# JETSON_AGX_DP-HDMI-USB-GBE.net
KiCad netlist of a schematic drawn in Altium Designer
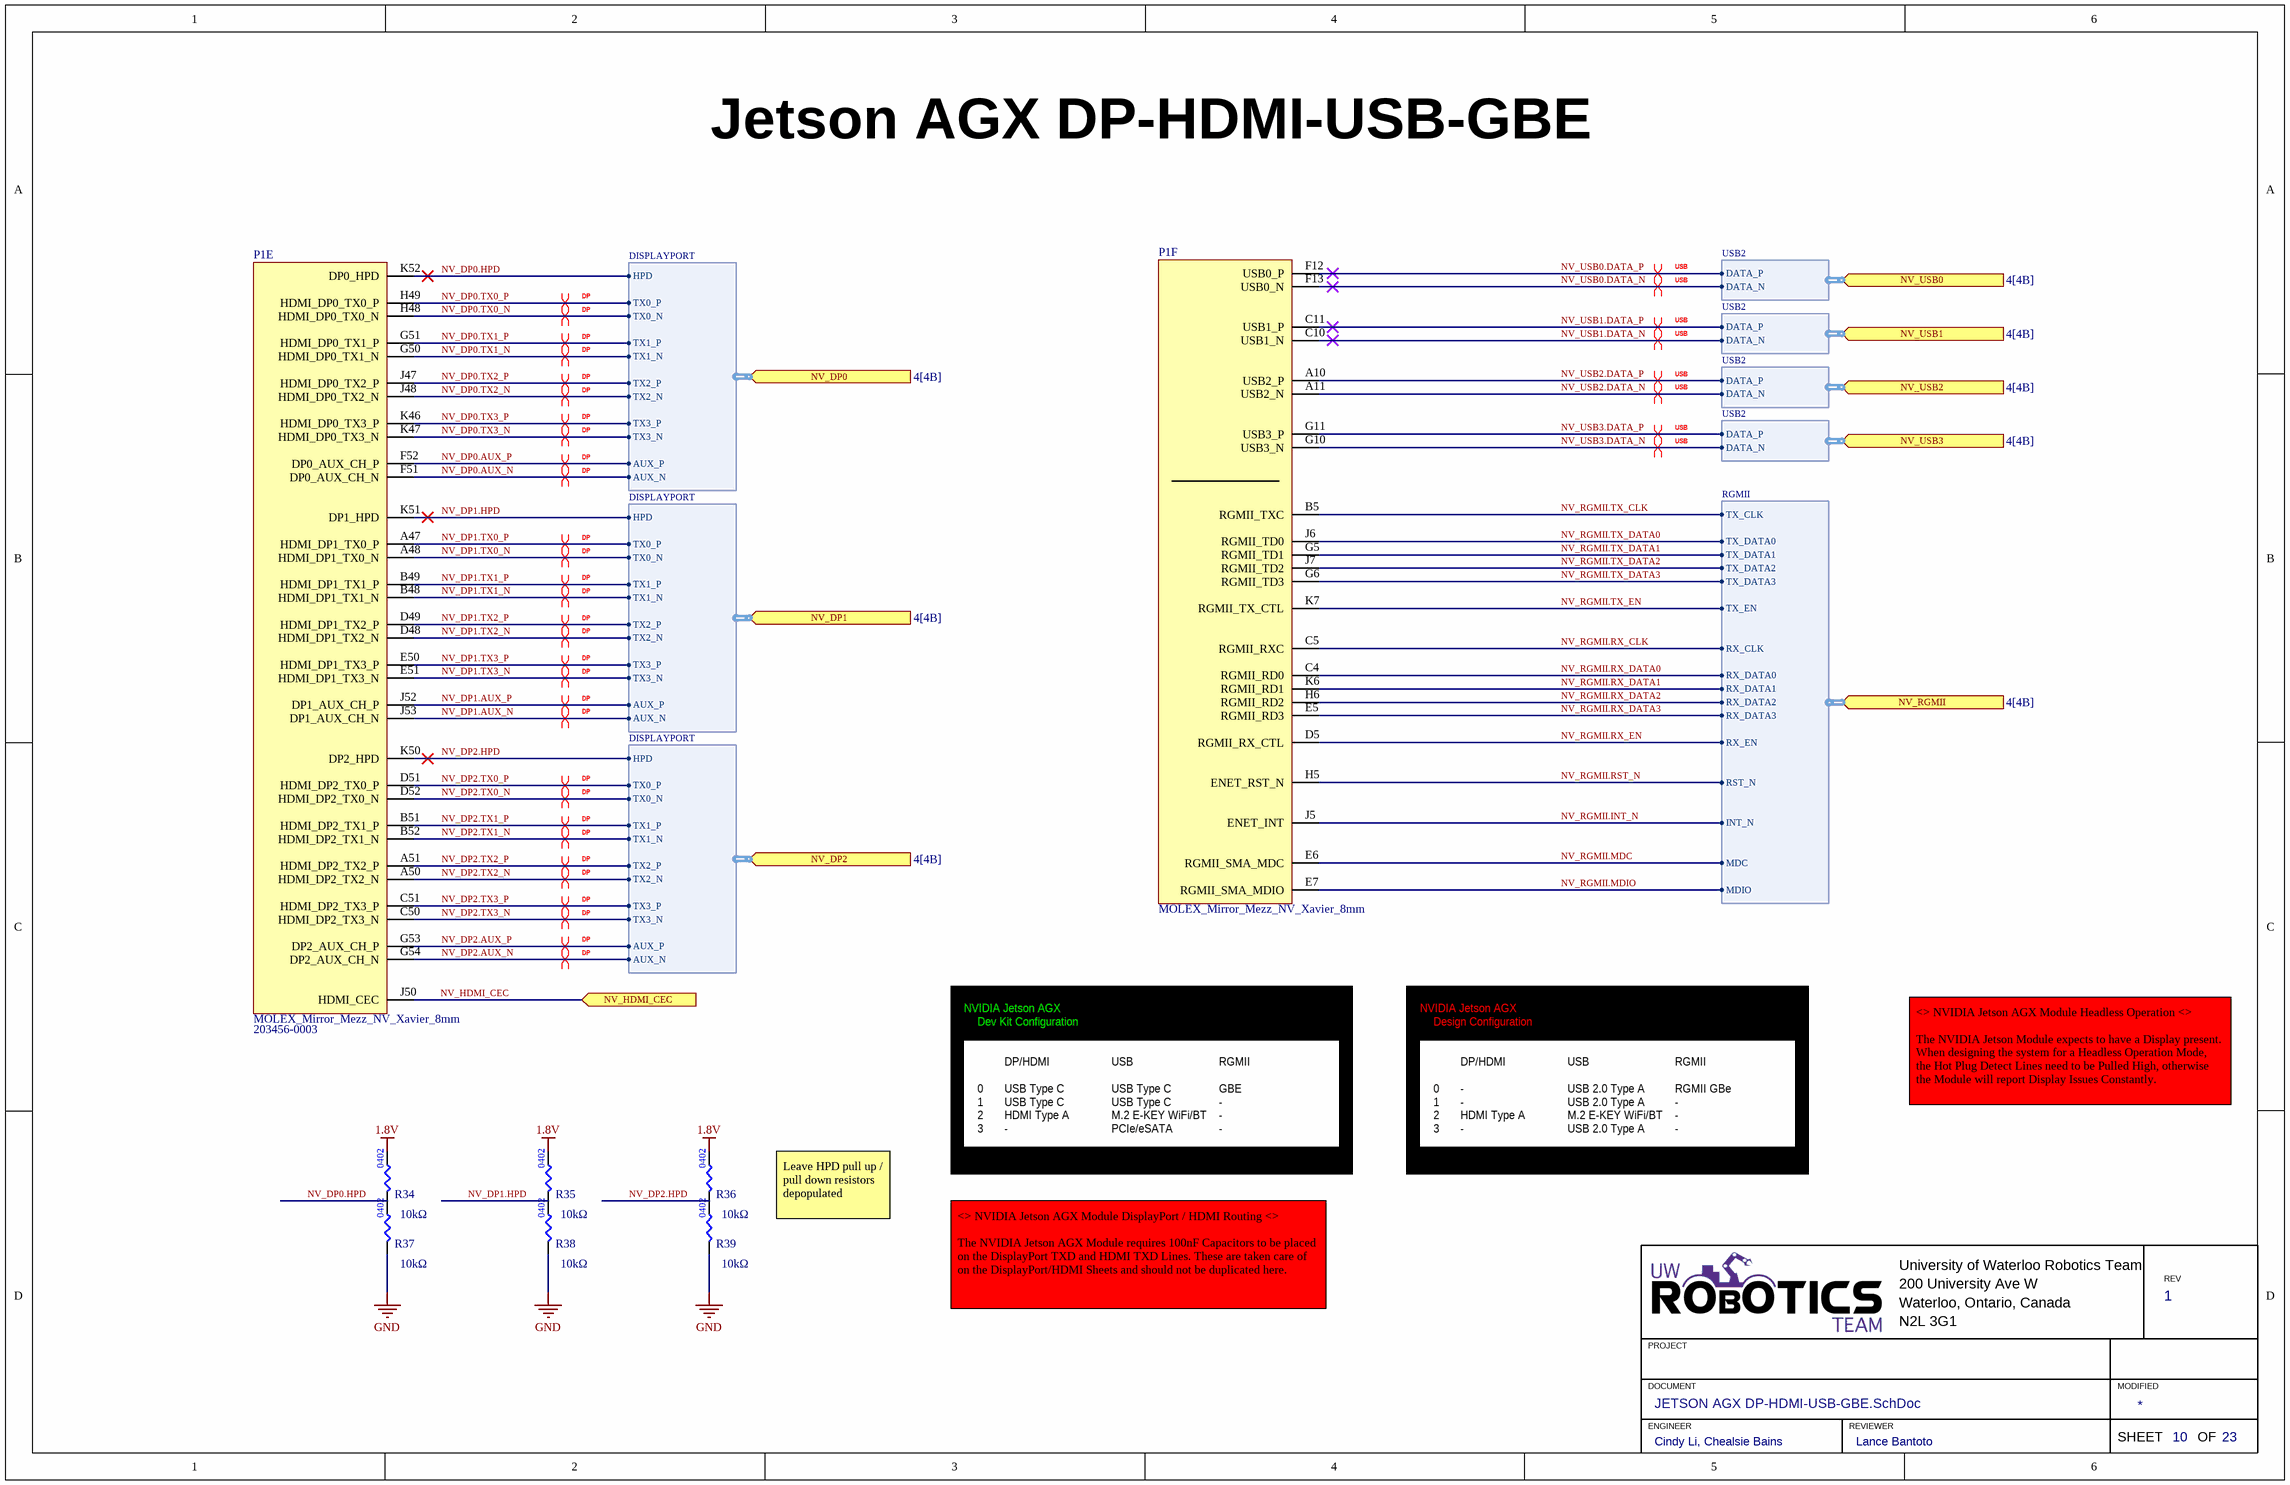
[diagram p0: JETSON AGX DP-HDMI-USB-GBE.SchDoc]

(export (version "E")
  (design (tool "Eeschema 10.0.6"))
  (components
    (comp (ref "P1")
      (value "MOLEX_Mirror_Mezz_NV_Xavier_8mm")
      (footprint "203456-0003")
      (description "CONN SELF-MATE 699POS SMD GOLD")
      (fields (field (name "MANUFACTURER PART NUMBER 1") "203456-0003"))
      (libsource (lib "UWRT_Schematic_Library_2020") (part "MOLEX_Mirror_Mezz_NV_Xavier_8mm"))
    )
    (comp (ref "R34")
      (value "RES_10kΩ_0402_1%")
      (footprint "RES0402")
      (description "RES 10K OHM 1% 1/16W 0402")
      (fields (field (name "TOLERANCE") "1%") (field (name "RESISTANCE") "10kΩ"))
      (libsource (lib "UWRT_Schematic_Library_2020") (part "RES_10kΩ_0402_1%"))
    )
    (comp (ref "R35")
      (value "RES_10kΩ_0402_1%")
      (footprint "RES0402")
      (description "RES 10K OHM 1% 1/16W 0402")
      (fields (field (name "TOLERANCE") "1%") (field (name "RESISTANCE") "10kΩ"))
      (libsource (lib "UWRT_Schematic_Library_2020") (part "RES_10kΩ_0402_1%"))
    )
    (comp (ref "R36")
      (value "RES_10kΩ_0402_1%")
      (footprint "RES0402")
      (description "RES 10K OHM 1% 1/16W 0402")
      (fields (field (name "TOLERANCE") "1%") (field (name "RESISTANCE") "10kΩ"))
      (libsource (lib "UWRT_Schematic_Library_2020") (part "RES_10kΩ_0402_1%"))
    )
    (comp (ref "R37")
      (value "RES_10kΩ_0402_1%")
      (footprint "RES0402")
      (description "RES 10K OHM 1% 1/16W 0402")
      (fields (field (name "TOLERANCE") "1%") (field (name "RESISTANCE") "10kΩ"))
      (libsource (lib "UWRT_Schematic_Library_2020") (part "RES_10kΩ_0402_1%"))
    )
    (comp (ref "R38")
      (value "RES_10kΩ_0402_1%")
      (footprint "RES0402")
      (description "RES 10K OHM 1% 1/16W 0402")
      (fields (field (name "TOLERANCE") "1%") (field (name "RESISTANCE") "10kΩ"))
      (libsource (lib "UWRT_Schematic_Library_2020") (part "RES_10kΩ_0402_1%"))
    )
    (comp (ref "R39")
      (value "RES_10kΩ_0402_1%")
      (footprint "RES0402")
      (description "RES 10K OHM 1% 1/16W 0402")
      (fields (field (name "TOLERANCE") "1%") (field (name "RESISTANCE") "10kΩ"))
      (libsource (lib "UWRT_Schematic_Library_2020") (part "RES_10kΩ_0402_1%"))
    )
  )
  (nets
    (net (code "4") (name "/NV_DP0.AUX_N") (class "Default")
      (node (ref "P1") (pin "F51") (pinfunction "DP0_AUX_CH_N_F51") (pintype "passive"))
    )
    (net (code "5") (name "/NV_DP0.AUX_P") (class "Default")
      (node (ref "P1") (pin "F52") (pinfunction "DP0_AUX_CH_P_F52") (pintype "passive"))
    )
    (net (code "6") (name "/NV_DP0.HPD") (class "Default")
      (node (ref "P1") (pin "K52") (pinfunction "DP0_HPD_K52") (pintype "passive"))
      (node (ref "R37") (pin "2") (pinfunction "2_2") (pintype "passive"))
    )
    (net (code "7") (name "/NV_DP0.TX0_N") (class "Default")
      (node (ref "P1") (pin "H48") (pinfunction "HDMI_DP0_TX0_N_H48") (pintype "passive"))
    )
    (net (code "8") (name "/NV_DP0.TX0_P") (class "Default")
      (node (ref "P1") (pin "H49") (pinfunction "HDMI_DP0_TX0_P_H49") (pintype "passive"))
    )
    (net (code "9") (name "/NV_DP0.TX1_N") (class "Default")
      (node (ref "P1") (pin "G50") (pinfunction "HDMI_DP0_TX1_N_G50") (pintype "passive"))
    )
    (net (code "10") (name "/NV_DP0.TX1_P") (class "Default")
      (node (ref "P1") (pin "G51") (pinfunction "HDMI_DP0_TX1_P_G51") (pintype "passive"))
    )
    (net (code "11") (name "/NV_DP0.TX2_N") (class "Default")
      (node (ref "P1") (pin "J48") (pinfunction "HDMI_DP0_TX2_N_J48") (pintype "passive"))
    )
    (net (code "12") (name "/NV_DP0.TX2_P") (class "Default")
      (node (ref "P1") (pin "J47") (pinfunction "HDMI_DP0_TX2_P_J47") (pintype "passive"))
    )
    (net (code "13") (name "/NV_DP0.TX3_N") (class "Default")
      (node (ref "P1") (pin "K47") (pinfunction "HDMI_DP0_TX3_N_K47") (pintype "passive"))
    )
    (net (code "14") (name "/NV_DP0.TX3_P") (class "Default")
      (node (ref "P1") (pin "K46") (pinfunction "HDMI_DP0_TX3_P_K46") (pintype "passive"))
    )
    (net (code "15") (name "/NV_DP1.AUX_N") (class "Default")
      (node (ref "P1") (pin "J53") (pinfunction "DP1_AUX_CH_N_J53") (pintype "passive"))
    )
    (net (code "16") (name "/NV_DP1.AUX_P") (class "Default")
      (node (ref "P1") (pin "J52") (pinfunction "DP1_AUX_CH_P_J52") (pintype "passive"))
    )
    (net (code "17") (name "/NV_DP1.HPD") (class "Default")
      (node (ref "P1") (pin "K51") (pinfunction "DP1_HPD_K51") (pintype "passive"))
      (node (ref "R38") (pin "2") (pinfunction "2_2") (pintype "passive"))
    )
    (net (code "18") (name "/NV_DP1.TX0_N") (class "Default")
      (node (ref "P1") (pin "A48") (pinfunction "HDMI_DP1_TX0_N_A48") (pintype "passive"))
    )
    (net (code "19") (name "/NV_DP1.TX0_P") (class "Default")
      (node (ref "P1") (pin "A47") (pinfunction "HDMI_DP1_TX0_P_A47") (pintype "passive"))
    )
    (net (code "20") (name "/NV_DP1.TX1_N") (class "Default")
      (node (ref "P1") (pin "B48") (pinfunction "HDMI_DP1_TX1_N_B48") (pintype "passive"))
    )
    (net (code "21") (name "/NV_DP1.TX1_P") (class "Default")
      (node (ref "P1") (pin "B49") (pinfunction "HDMI_DP1_TX1_P_B49") (pintype "passive"))
    )
    (net (code "22") (name "/NV_DP1.TX2_N") (class "Default")
      (node (ref "P1") (pin "D48") (pinfunction "HDMI_DP1_TX2_N_D48") (pintype "passive"))
    )
    (net (code "23") (name "/NV_DP1.TX2_P") (class "Default")
      (node (ref "P1") (pin "D49") (pinfunction "HDMI_DP1_TX2_P_D49") (pintype "passive"))
    )
    (net (code "24") (name "/NV_DP1.TX3_N") (class "Default")
      (node (ref "P1") (pin "E51") (pinfunction "HDMI_DP1_TX3_N_E51") (pintype "passive"))
    )
    (net (code "25") (name "/NV_DP1.TX3_P") (class "Default")
      (node (ref "P1") (pin "E50") (pinfunction "HDMI_DP1_TX3_P_E50") (pintype "passive"))
    )
    (net (code "26") (name "/NV_DP2.AUX_N") (class "Default")
      (node (ref "P1") (pin "G54") (pinfunction "DP2_AUX_CH_N_G54") (pintype "passive"))
    )
    (net (code "27") (name "/NV_DP2.AUX_P") (class "Default")
      (node (ref "P1") (pin "G53") (pinfunction "DP2_AUX_CH_P_G53") (pintype "passive"))
    )
    (net (code "28") (name "/NV_DP2.HPD") (class "Default")
      (node (ref "P1") (pin "K50") (pinfunction "DP2_HPD_K50") (pintype "passive"))
      (node (ref "R39") (pin "2") (pinfunction "2_2") (pintype "passive"))
    )
    (net (code "29") (name "/NV_DP2.TX0_N") (class "Default")
      (node (ref "P1") (pin "D52") (pinfunction "HDMI_DP2_TX0_N_D52") (pintype "passive"))
    )
    (net (code "30") (name "/NV_DP2.TX0_P") (class "Default")
      (node (ref "P1") (pin "D51") (pinfunction "HDMI_DP2_TX0_P_D51") (pintype "passive"))
    )
    (net (code "31") (name "/NV_DP2.TX1_N") (class "Default")
      (node (ref "P1") (pin "B52") (pinfunction "HDMI_DP2_TX1_N_B52") (pintype "passive"))
    )
    (net (code "32") (name "/NV_DP2.TX1_P") (class "Default")
      (node (ref "P1") (pin "B51") (pinfunction "HDMI_DP2_TX1_P_B51") (pintype "passive"))
    )
    (net (code "33") (name "/NV_DP2.TX2_N") (class "Default")
      (node (ref "P1") (pin "A50") (pinfunction "HDMI_DP2_TX2_N_A50") (pintype "passive"))
    )
    (net (code "34") (name "/NV_DP2.TX2_P") (class "Default")
      (node (ref "P1") (pin "A51") (pinfunction "HDMI_DP2_TX2_P_A51") (pintype "passive"))
    )
    (net (code "35") (name "/NV_DP2.TX3_N") (class "Default")
      (node (ref "P1") (pin "C50") (pinfunction "HDMI_DP2_TX3_N_C50") (pintype "passive"))
    )
    (net (code "36") (name "/NV_DP2.TX3_P") (class "Default")
      (node (ref "P1") (pin "C51") (pinfunction "HDMI_DP2_TX3_P_C51") (pintype "passive"))
    )
    (net (code "37") (name "/NV_HDMI_CEC") (class "Default")
      (node (ref "P1") (pin "J50") (pinfunction "HDMI_CEC_J50") (pintype "passive"))
    )
    (net (code "38") (name "/NV_RGMII.INT_N") (class "Default")
      (node (ref "P1") (pin "J5") (pinfunction "ENET_INT_J5") (pintype "passive"))
    )
    (net (code "39") (name "/NV_RGMII.MDC") (class "Default")
      (node (ref "P1") (pin "E6") (pinfunction "RGMII_SMA_MDC_E6") (pintype "passive"))
    )
    (net (code "40") (name "/NV_RGMII.MDIO") (class "Default")
      (node (ref "P1") (pin "E7") (pinfunction "RGMII_SMA_MDIO_E7") (pintype "passive"))
    )
    (net (code "41") (name "/NV_RGMII.RST_N") (class "Default")
      (node (ref "P1") (pin "H5") (pinfunction "ENET_RST_N_H5") (pintype "passive"))
    )
    (net (code "42") (name "/NV_RGMII.RX_CLK") (class "Default")
      (node (ref "P1") (pin "C5") (pinfunction "RGMII_RXC_C5") (pintype "passive"))
    )
    (net (code "43") (name "/NV_RGMII.RX_DATA0") (class "Default")
      (node (ref "P1") (pin "C4") (pinfunction "RGMII_RD0_C4") (pintype "passive"))
    )
    (net (code "44") (name "/NV_RGMII.RX_DATA1") (class "Default")
      (node (ref "P1") (pin "K6") (pinfunction "RGMII_RD1_K6") (pintype "passive"))
    )
    (net (code "45") (name "/NV_RGMII.RX_DATA2") (class "Default")
      (node (ref "P1") (pin "H6") (pinfunction "RGMII_RD2_H6") (pintype "passive"))
    )
    (net (code "46") (name "/NV_RGMII.RX_DATA3") (class "Default")
      (node (ref "P1") (pin "E5") (pinfunction "RGMII_RD3_E5") (pintype "passive"))
    )
    (net (code "47") (name "/NV_RGMII.RX_EN") (class "Default")
      (node (ref "P1") (pin "D5") (pinfunction "RGMII_RX_CTL_D5") (pintype "passive"))
    )
    (net (code "48") (name "/NV_RGMII.TX_CLK") (class "Default")
      (node (ref "P1") (pin "B5") (pinfunction "RGMII_TXC_B5") (pintype "passive"))
    )
    (net (code "49") (name "/NV_RGMII.TX_DATA0") (class "Default")
      (node (ref "P1") (pin "J6") (pinfunction "RGMII_TD0_J6") (pintype "passive"))
    )
    (net (code "50") (name "/NV_RGMII.TX_DATA1") (class "Default")
      (node (ref "P1") (pin "G5") (pinfunction "RGMII_TD1_G5") (pintype "passive"))
    )
    (net (code "51") (name "/NV_RGMII.TX_DATA2") (class "Default")
      (node (ref "P1") (pin "J7") (pinfunction "RGMII_TD2_J7") (pintype "passive"))
    )
    (net (code "52") (name "/NV_RGMII.TX_DATA3") (class "Default")
      (node (ref "P1") (pin "G6") (pinfunction "RGMII_TD3_G6") (pintype "passive"))
    )
    (net (code "53") (name "/NV_RGMII.TX_EN") (class "Default")
      (node (ref "P1") (pin "K7") (pinfunction "RGMII_TX_CTL_K7") (pintype "passive"))
    )
    (net (code "54") (name "/NV_USB0.DATA_N") (class "Default")
      (node (ref "P1") (pin "F13") (pinfunction "USB0_N_F13") (pintype "passive"))
    )
    (net (code "55") (name "/NV_USB0.DATA_P") (class "Default")
      (node (ref "P1") (pin "F12") (pinfunction "USB0_P_F12") (pintype "passive"))
    )
    (net (code "56") (name "/NV_USB1.DATA_N") (class "Default")
      (node (ref "P1") (pin "C10") (pinfunction "USB1_N_C10") (pintype "passive"))
    )
    (net (code "57") (name "/NV_USB1.DATA_P") (class "Default")
      (node (ref "P1") (pin "C11") (pinfunction "USB1_P_C11") (pintype "passive"))
    )
    (net (code "58") (name "/NV_USB2.DATA_N") (class "Default")
      (node (ref "P1") (pin "A11") (pinfunction "USB2_N_A11") (pintype "passive"))
    )
    (net (code "59") (name "/NV_USB2.DATA_P") (class "Default")
      (node (ref "P1") (pin "A10") (pinfunction "USB2_P_A10") (pintype "passive"))
    )
    (net (code "60") (name "/NV_USB3.DATA_N") (class "Default")
      (node (ref "P1") (pin "G10") (pinfunction "USB3_N_G10") (pintype "passive"))
    )
    (net (code "61") (name "/NV_USB3.DATA_P") (class "Default")
      (node (ref "P1") (pin "G11") (pinfunction "USB3_P_G11") (pintype "passive"))
    )
    (net (code "65") (name "1.8V") (class "Default")
      (node (ref "R34") (pin "2") (pinfunction "2_2") (pintype "passive"))
      (node (ref "R35") (pin "2") (pinfunction "2_2") (pintype "passive"))
      (node (ref "R36") (pin "2") (pinfunction "2_2") (pintype "passive"))
    )
    (net (code "66") (name "GND") (class "Default")
      (node (ref "R37") (pin "1") (pinfunction "1_1") (pintype "passive"))
      (node (ref "R38") (pin "1") (pinfunction "1_1") (pintype "passive"))
      (node (ref "R39") (pin "1") (pinfunction "1_1") (pintype "passive"))
    )
    (net (code "67") (name "unconnected-(R34-Pad1)") (class "Default")
      (node (ref "R34") (pin "1") (pinfunction "1_1") (pintype "passive"))
    )
    (net (code "68") (name "unconnected-(R35-Pad1)") (class "Default")
      (node (ref "R35") (pin "1") (pinfunction "1_1") (pintype "passive"))
    )
    (net (code "69") (name "unconnected-(R36-Pad1)") (class "Default")
      (node (ref "R36") (pin "1") (pinfunction "1_1") (pintype "passive"))
    )
  )
)
